# PrimaryBoard.net
KiCad netlist of a schematic drawn in EAGLE
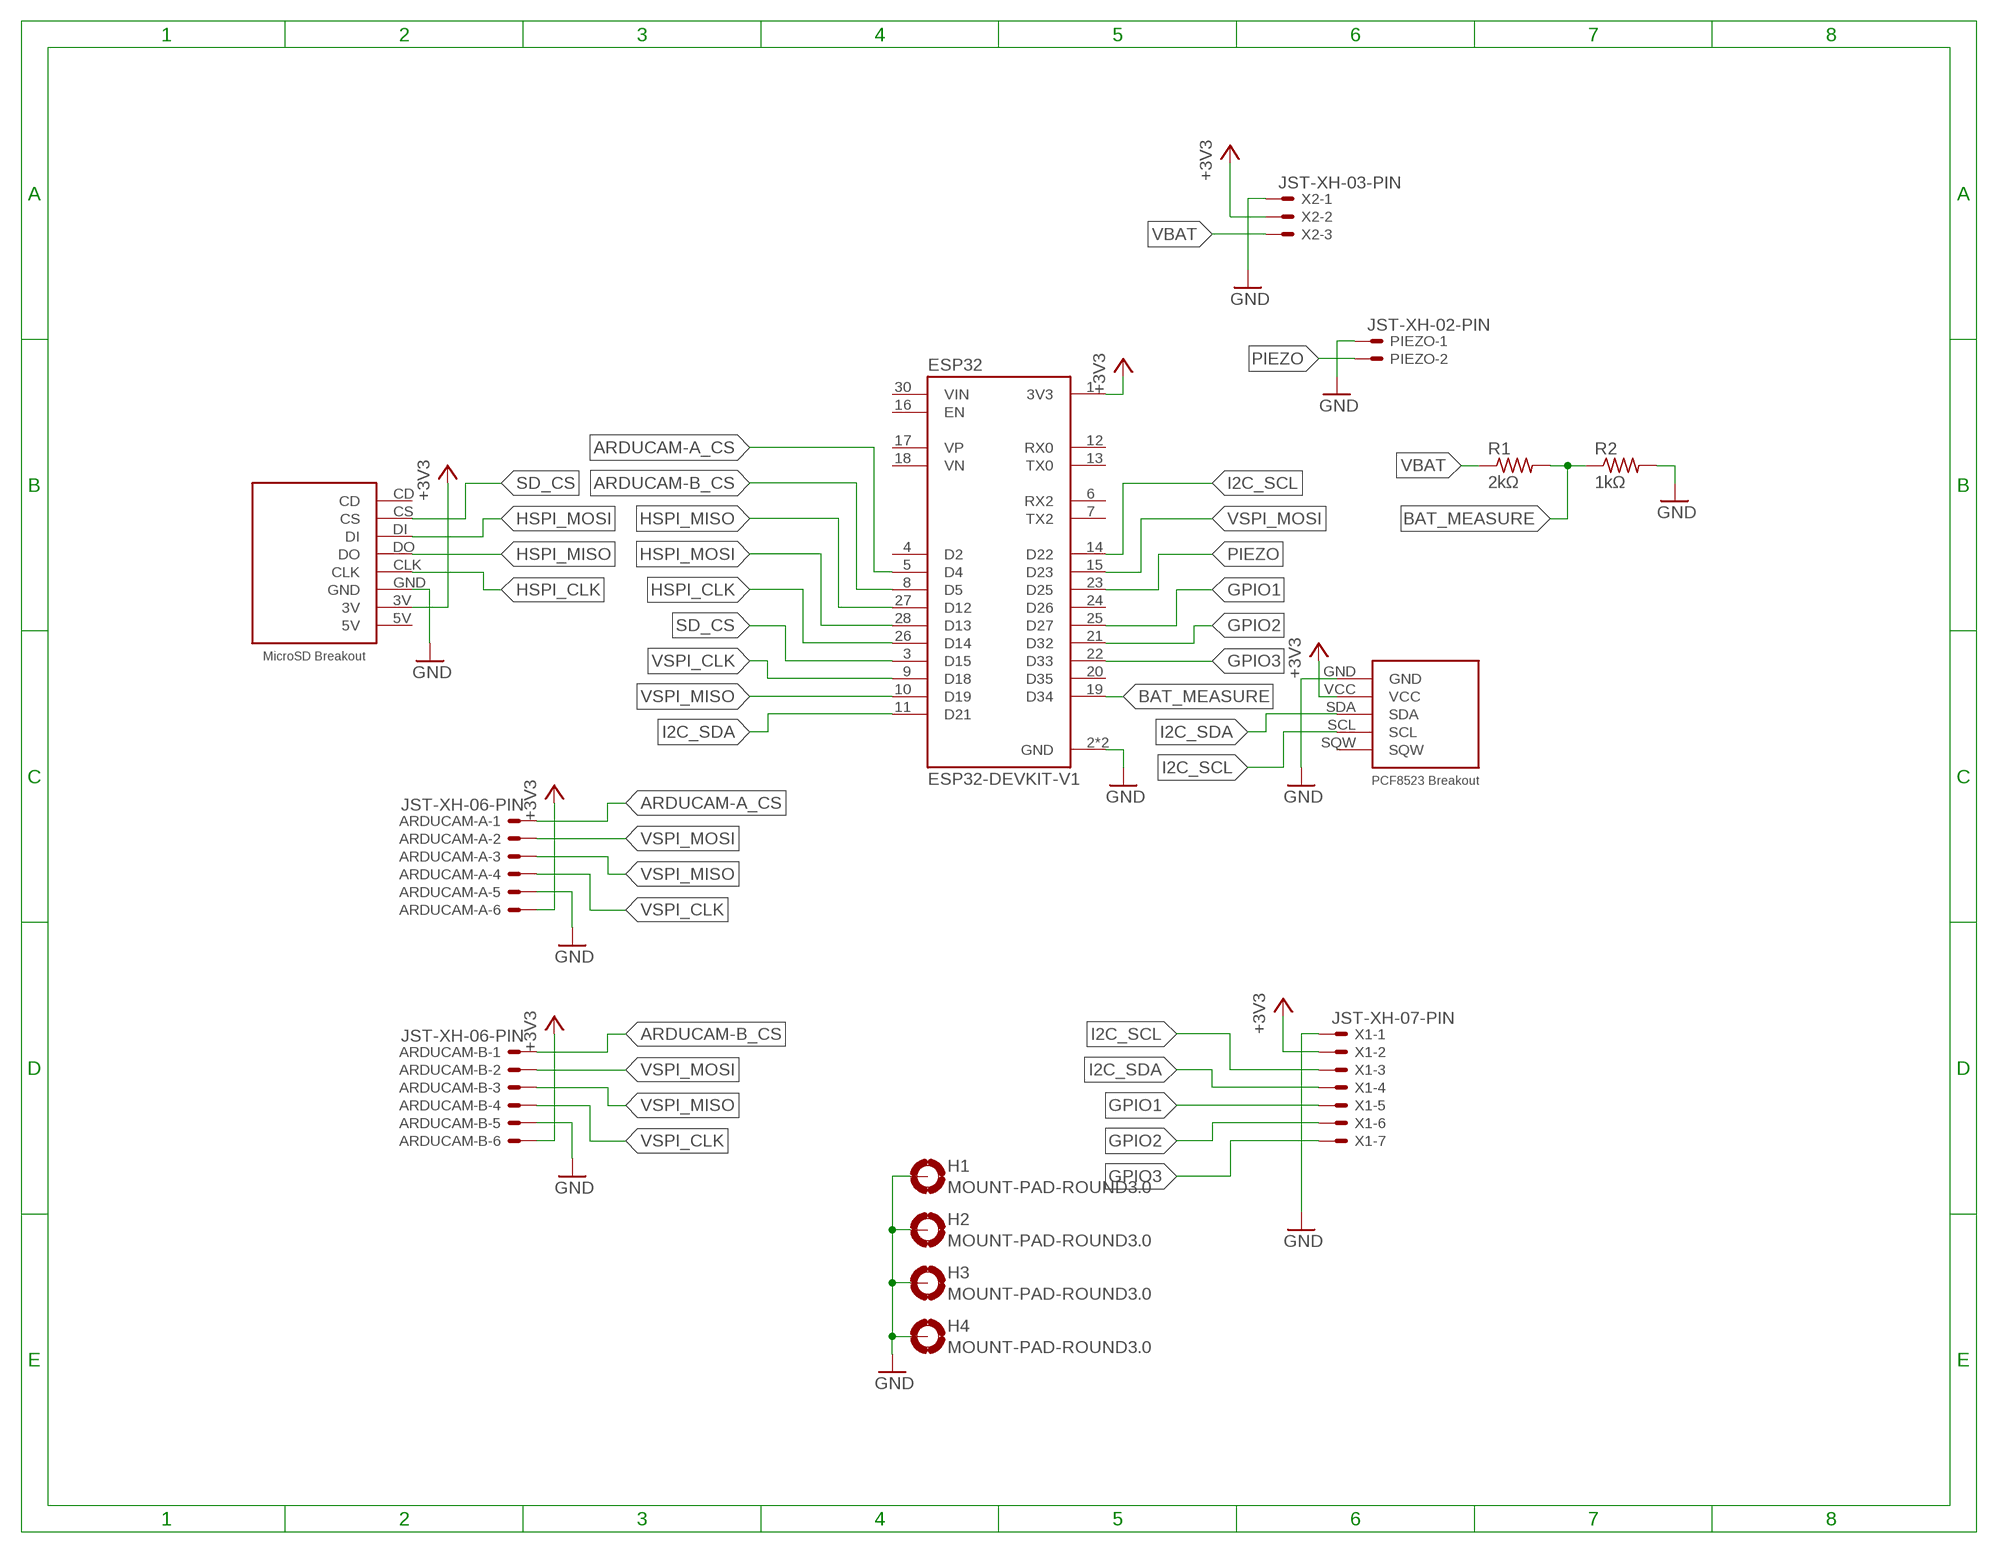
[diagram p0: schematic, sheet 1]

(export (version "E")
  (design (tool "Eeschema 10.0.6"))
  (components
    (comp (ref "ARDUCAM-A")
      (value "JST-XH-06-PIN")
      (footprint "eagle-import:JST-XH_S6B")
      (libsource (lib "eagle-import") (part "JST-XH-06-PIN"))
    )
    (comp (ref "ARDUCAM-B")
      (value "JST-XH-06-PIN")
      (footprint "eagle-import:JST-XH_S6B")
      (libsource (lib "eagle-import") (part "JST-XH-06-PIN"))
    )
    (comp (ref "ESP32")
      (value "ESP32-DEVKIT-V1")
      (footprint "eagle-import:MODULE_ESP32_DEVKIT_V1")
      (fields (field (name "MF") "Do it"))
      (libsource (lib "eagle-import") (part "ESP32-DEVKIT-V1"))
    )
    (comp (ref "H1")
      (value "MOUNT-PAD-ROUND3.0")
      (footprint "eagle-import:3,0-PAD")
      (libsource (lib "eagle-import") (part "MOUNT-PAD-ROUND3.0"))
    )
    (comp (ref "H2")
      (value "MOUNT-PAD-ROUND3.0")
      (footprint "eagle-import:3,0-PAD")
      (libsource (lib "eagle-import") (part "MOUNT-PAD-ROUND3.0"))
    )
    (comp (ref "H3")
      (value "MOUNT-PAD-ROUND3.0")
      (footprint "eagle-import:3,0-PAD")
      (libsource (lib "eagle-import") (part "MOUNT-PAD-ROUND3.0"))
    )
    (comp (ref "H4")
      (value "MOUNT-PAD-ROUND3.0")
      (footprint "eagle-import:3,0-PAD")
      (libsource (lib "eagle-import") (part "MOUNT-PAD-ROUND3.0"))
    )
    (comp (ref "PIEZO")
      (value "JST-XH-02-PIN")
      (footprint "eagle-import:JST-XH_S2B")
      (libsource (lib "eagle-import") (part "JST-XH-02-PIN"))
    )
    (comp (ref "R1")
      (value "2kΩ")
      (footprint "eagle-import:0207_10")
      (libsource (lib "eagle-import") (part "R-US_0207/10"))
    )
    (comp (ref "R2")
      (value "1kΩ")
      (footprint "eagle-import:0207_10")
      (libsource (lib "eagle-import") (part "R-US_0207/10"))
    )
    (comp (ref "U$1")
      (value "MICROSDBREAKOUT5V")
      (footprint "eagle-import:MICROSDBREAKOUT5V")
      (libsource (lib "eagle-import") (part "MICROSDBREAKOUT5V"))
    )
    (comp (ref "U$2")
      (value "PCF8523BREAKOUT")
      (footprint "eagle-import:PCF8523BREAKOUT")
      (libsource (lib "eagle-import") (part "PCF8523BREAKOUT"))
    )
    (comp (ref "X1")
      (value "JST-XH-07-PIN")
      (footprint "eagle-import:JST-XH_S7B")
      (libsource (lib "eagle-import") (part "JST-XH-07-PIN"))
    )
    (comp (ref "X2")
      (value "JST-XH-03-PIN")
      (footprint "eagle-import:JST-XH_S3B")
      (libsource (lib "eagle-import") (part "JST-XH-03-PIN"))
    )
  )
  (nets
    (net (code "1") (name "+3V3") (class "Default")
      (node (ref "ARDUCAM-A") (pin "PIN6") (pinfunction "S_PIN6") (pintype "passive"))
      (node (ref "ARDUCAM-B") (pin "PIN6") (pinfunction "S_PIN6") (pintype "passive"))
      (node (ref "ESP32") (pin "1") (pinfunction "3V3_1") (pintype "output"))
      (node (ref "U$1") (pin "3V") (pinfunction "3V_3V") (pintype "bidirectional"))
      (node (ref "U$2") (pin "VCC") (pinfunction "VCC_VCC") (pintype "bidirectional"))
      (node (ref "X1") (pin "PIN2") (pinfunction "S_PIN2") (pintype "passive"))
      (node (ref "X2") (pin "PIN2") (pinfunction "S_PIN2") (pintype "passive"))
    )
    (net (code "2") (name "ARDUCAM-A_CS") (class "Default")
      (node (ref "ARDUCAM-A") (pin "PIN1") (pinfunction "S_PIN1") (pintype "passive"))
      (node (ref "ESP32") (pin "5") (pinfunction "D4_5") (pintype "bidirectional"))
    )
    (net (code "3") (name "ARDUCAM-B_CS") (class "Default")
      (node (ref "ARDUCAM-B") (pin "PIN1") (pinfunction "S_PIN1") (pintype "passive"))
      (node (ref "ESP32") (pin "8") (pinfunction "D5_8") (pintype "bidirectional"))
    )
    (net (code "4") (name "BAT_MEASURE") (class "Default")
      (node (ref "ESP32") (pin "19") (pinfunction "D34_19") (pintype "bidirectional"))
      (node (ref "R1") (pin "2") (pinfunction "2_2") (pintype "passive"))
      (node (ref "R2") (pin "1") (pinfunction "1_1") (pintype "passive"))
    )
    (net (code "5") (name "GND") (class "Default")
      (node (ref "ARDUCAM-A") (pin "PIN5") (pinfunction "S_PIN5") (pintype "passive"))
      (node (ref "ARDUCAM-B") (pin "PIN5") (pinfunction "S_PIN5") (pintype "passive"))
      (node (ref "ESP32") (pin "2") (pinfunction "GND_2") (pintype "power_in"))
      (node (ref "ESP32") (pin "29") (pinfunction "GND_29") (pintype "power_in"))
      (node (ref "H1") (pin "B3,0") (pinfunction "MOUNT_B3,0") (pintype "passive"))
      (node (ref "H2") (pin "B3,0") (pinfunction "MOUNT_B3,0") (pintype "passive"))
      (node (ref "H3") (pin "B3,0") (pinfunction "MOUNT_B3,0") (pintype "passive"))
      (node (ref "H4") (pin "B3,0") (pinfunction "MOUNT_B3,0") (pintype "passive"))
      (node (ref "PIEZO") (pin "PIN1") (pinfunction "S_PIN1") (pintype "passive"))
      (node (ref "R2") (pin "2") (pinfunction "2_2") (pintype "passive"))
      (node (ref "U$1") (pin "GND") (pinfunction "GND_GND") (pintype "bidirectional"))
      (node (ref "U$2") (pin "GND") (pinfunction "GND_GND") (pintype "bidirectional"))
      (node (ref "X1") (pin "PIN1") (pinfunction "S_PIN1") (pintype "passive"))
      (node (ref "X2") (pin "PIN1") (pinfunction "S_PIN1") (pintype "passive"))
    )
    (net (code "6") (name "GPIO1") (class "Default")
      (node (ref "ESP32") (pin "25") (pinfunction "D27_25") (pintype "bidirectional"))
      (node (ref "X1") (pin "PIN5") (pinfunction "S_PIN5") (pintype "passive"))
    )
    (net (code "7") (name "GPIO2") (class "Default")
      (node (ref "ESP32") (pin "21") (pinfunction "D32_21") (pintype "bidirectional"))
      (node (ref "X1") (pin "PIN6") (pinfunction "S_PIN6") (pintype "passive"))
    )
    (net (code "8") (name "GPIO3") (class "Default")
      (node (ref "ESP32") (pin "22") (pinfunction "D33_22") (pintype "bidirectional"))
      (node (ref "X1") (pin "PIN7") (pinfunction "S_PIN7") (pintype "passive"))
    )
    (net (code "9") (name "HSPI_CLK") (class "Default")
      (node (ref "ESP32") (pin "26") (pinfunction "D14_26") (pintype "bidirectional"))
      (node (ref "U$1") (pin "CLK") (pinfunction "CLK_CLK") (pintype "bidirectional"))
    )
    (net (code "10") (name "HSPI_MISO") (class "Default")
      (node (ref "ESP32") (pin "27") (pinfunction "D12_27") (pintype "bidirectional"))
      (node (ref "U$1") (pin "DO") (pinfunction "DO_DO") (pintype "bidirectional"))
    )
    (net (code "11") (name "HSPI_MOSI") (class "Default")
      (node (ref "ESP32") (pin "28") (pinfunction "D13_28") (pintype "bidirectional"))
      (node (ref "U$1") (pin "DI") (pinfunction "DI_DI") (pintype "bidirectional"))
    )
    (net (code "12") (name "I2C_SCL") (class "Default")
      (node (ref "ESP32") (pin "14") (pinfunction "D22_14") (pintype "bidirectional"))
      (node (ref "U$2") (pin "SCL") (pinfunction "SCL_SCL") (pintype "bidirectional"))
      (node (ref "X1") (pin "PIN3") (pinfunction "S_PIN3") (pintype "passive"))
    )
    (net (code "13") (name "I2C_SDA") (class "Default")
      (node (ref "ESP32") (pin "11") (pinfunction "D21_11") (pintype "bidirectional"))
      (node (ref "U$2") (pin "SDA") (pinfunction "SDA_SDA") (pintype "bidirectional"))
      (node (ref "X1") (pin "PIN4") (pinfunction "S_PIN4") (pintype "passive"))
    )
    (net (code "14") (name "PIEZO") (class "Default")
      (node (ref "ESP32") (pin "23") (pinfunction "D25_23") (pintype "bidirectional"))
      (node (ref "PIEZO") (pin "PIN2") (pinfunction "S_PIN2") (pintype "passive"))
    )
    (net (code "15") (name "SD_CS") (class "Default")
      (node (ref "ESP32") (pin "3") (pinfunction "D15_3") (pintype "bidirectional"))
      (node (ref "U$1") (pin "CS") (pinfunction "CS_CS") (pintype "bidirectional"))
    )
    (net (code "16") (name "VBAT") (class "Default")
      (node (ref "R1") (pin "1") (pinfunction "1_1") (pintype "passive"))
      (node (ref "X2") (pin "PIN3") (pinfunction "S_PIN3") (pintype "passive"))
    )
    (net (code "17") (name "VSPI_CLK") (class "Default")
      (node (ref "ARDUCAM-A") (pin "PIN4") (pinfunction "S_PIN4") (pintype "passive"))
      (node (ref "ARDUCAM-B") (pin "PIN4") (pinfunction "S_PIN4") (pintype "passive"))
      (node (ref "ESP32") (pin "9") (pinfunction "D18_9") (pintype "bidirectional"))
    )
    (net (code "18") (name "VSPI_MISO") (class "Default")
      (node (ref "ARDUCAM-A") (pin "PIN3") (pinfunction "S_PIN3") (pintype "passive"))
      (node (ref "ARDUCAM-B") (pin "PIN3") (pinfunction "S_PIN3") (pintype "passive"))
      (node (ref "ESP32") (pin "10") (pinfunction "D19_10") (pintype "bidirectional"))
    )
    (net (code "19") (name "VSPI_MOSI") (class "Default")
      (node (ref "ARDUCAM-A") (pin "PIN2") (pinfunction "S_PIN2") (pintype "passive"))
      (node (ref "ARDUCAM-B") (pin "PIN2") (pinfunction "S_PIN2") (pintype "passive"))
      (node (ref "ESP32") (pin "15") (pinfunction "D23_15") (pintype "bidirectional"))
    )
    (net (code "20") (name "unconnected-(ESP32-D2-Pad4)") (class "Default")
      (node (ref "ESP32") (pin "4") (pinfunction "D2_4") (pintype "bidirectional"))
    )
    (net (code "21") (name "unconnected-(ESP32-D26-Pad24)") (class "Default")
      (node (ref "ESP32") (pin "24") (pinfunction "D26_24") (pintype "bidirectional"))
    )
    (net (code "22") (name "unconnected-(ESP32-D35-Pad20)") (class "Default")
      (node (ref "ESP32") (pin "20") (pinfunction "D35_20") (pintype "bidirectional"))
    )
    (net (code "23") (name "unconnected-(ESP32-EN-Pad16)") (class "Default")
      (node (ref "ESP32") (pin "16") (pinfunction "EN_16") (pintype "input"))
    )
    (net (code "24") (name "unconnected-(ESP32-RX0-Pad12)") (class "Default")
      (node (ref "ESP32") (pin "12") (pinfunction "RX0_12") (pintype "input"))
    )
    (net (code "25") (name "unconnected-(ESP32-RX2-Pad6)") (class "Default")
      (node (ref "ESP32") (pin "6") (pinfunction "RX2_6") (pintype "input"))
    )
    (net (code "26") (name "unconnected-(ESP32-TX0-Pad13)") (class "Default")
      (node (ref "ESP32") (pin "13") (pinfunction "TX0_13") (pintype "output"))
    )
    (net (code "27") (name "unconnected-(ESP32-TX2-Pad7)") (class "Default")
      (node (ref "ESP32") (pin "7") (pinfunction "TX2_7") (pintype "output"))
    )
    (net (code "28") (name "unconnected-(ESP32-VIN-Pad30)") (class "Default")
      (node (ref "ESP32") (pin "30") (pinfunction "VIN_30") (pintype "input"))
    )
    (net (code "29") (name "unconnected-(ESP32-VN-Pad18)") (class "Default")
      (node (ref "ESP32") (pin "18") (pinfunction "VN_18") (pintype "bidirectional"))
    )
    (net (code "30") (name "unconnected-(ESP32-VP-Pad17)") (class "Default")
      (node (ref "ESP32") (pin "17") (pinfunction "VP_17") (pintype "bidirectional"))
    )
    (net (code "31") (name "unconnected-(U$1-Pad5V)") (class "Default")
      (node (ref "U$1") (pin "5V") (pinfunction "5V_5V") (pintype "bidirectional"))
    )
    (net (code "32") (name "unconnected-(U$1-PadCD)") (class "Default")
      (node (ref "U$1") (pin "CD") (pinfunction "CD_CD") (pintype "bidirectional"))
    )
    (net (code "33") (name "unconnected-(U$2-PadSQW)") (class "Default")
      (node (ref "U$2") (pin "SQW") (pinfunction "SQW_SQW") (pintype "bidirectional"))
    )
  )
)
